# R7FA2E1A7_LED.net
KiCad netlist of a schematic drawn in EasyEDA Pro
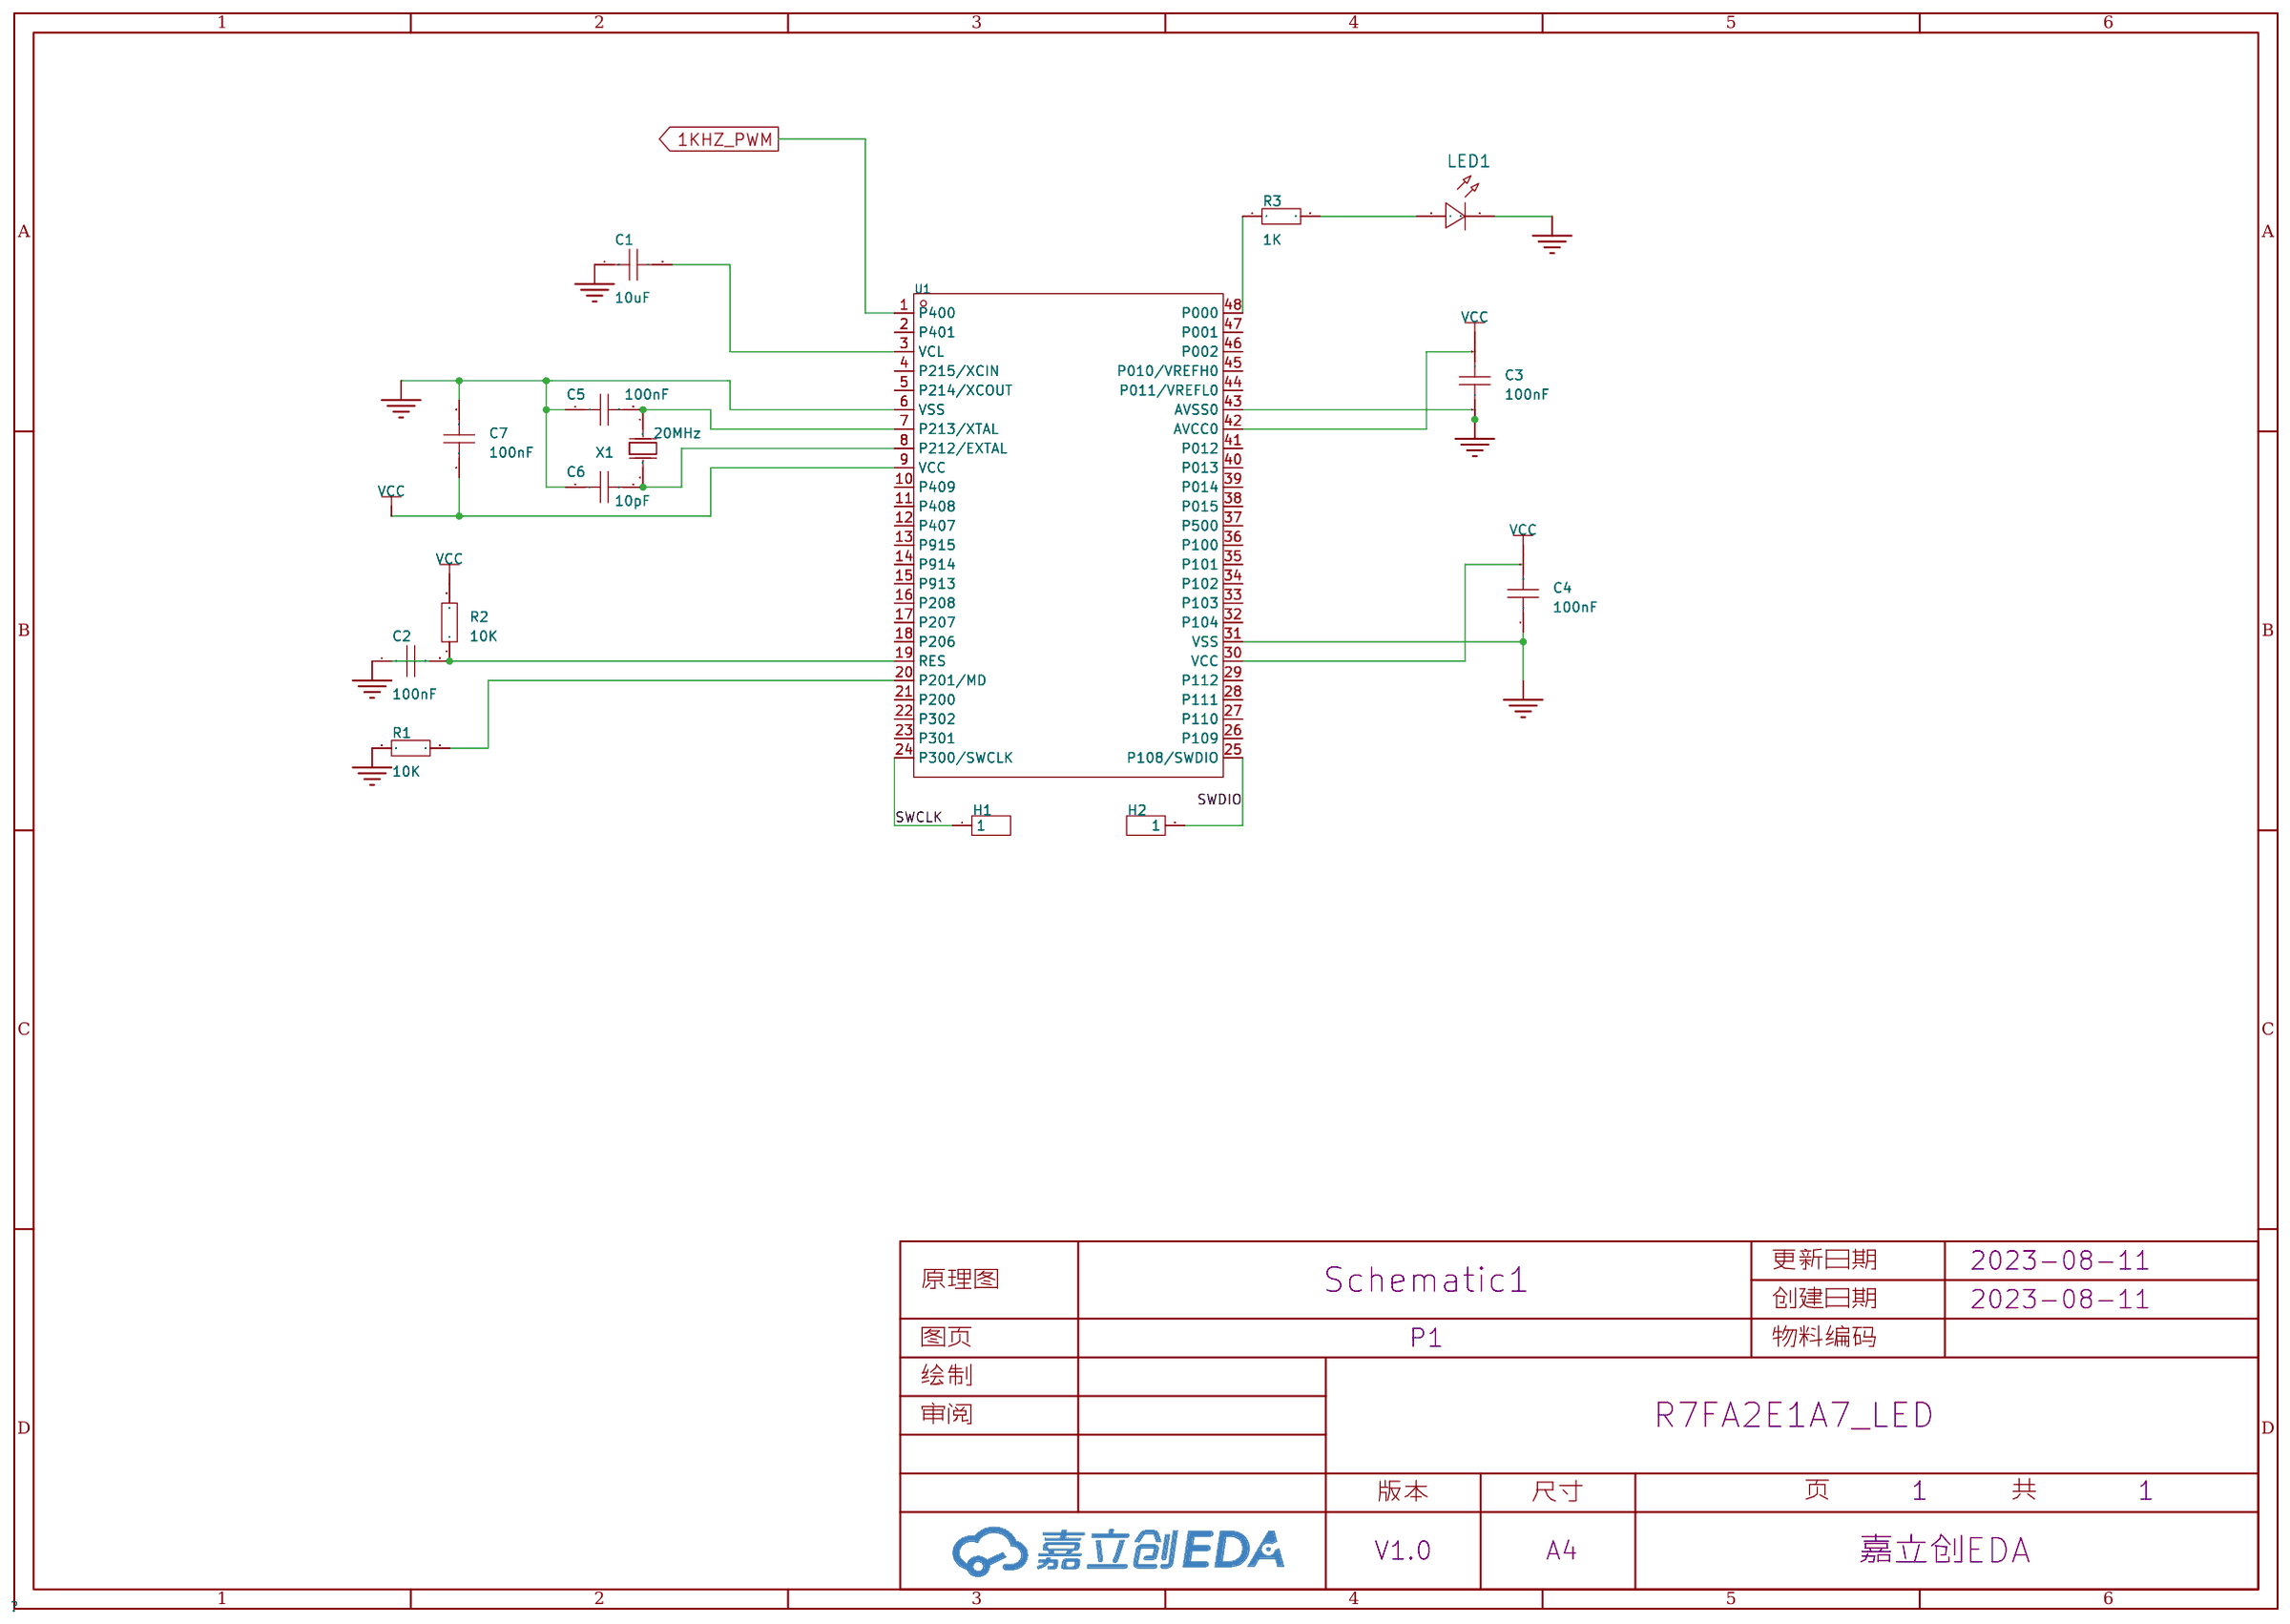
[diagram p0: schematic sheet]

(export (version "E")
  (design (tool "Eeschema 10.0.6"))
  (components
    (comp (ref "C1")
      (value "10uF")
      (footprint "easyedapro:C0603")
      (libsource (lib "easyedapro") (part "CapAcitance"))
    )
    (comp (ref "C2")
      (value "100nF")
      (footprint "easyedapro:C0603")
      (libsource (lib "easyedapro") (part "CapAcitance"))
    )
    (comp (ref "C3")
      (value "100nF")
      (footprint "easyedapro:C0603")
      (libsource (lib "easyedapro") (part "CapAcitance"))
    )
    (comp (ref "C4")
      (value "100nF")
      (footprint "easyedapro:C0603")
      (libsource (lib "easyedapro") (part "CapAcitance"))
    )
    (comp (ref "C5")
      (value "100nF")
      (footprint "easyedapro:C0603")
      (libsource (lib "easyedapro") (part "CapAcitance"))
    )
    (comp (ref "C6")
      (value "10pF")
      (footprint "easyedapro:C0603")
      (libsource (lib "easyedapro") (part "CapAcitance"))
    )
    (comp (ref "C7")
      (value "100nF")
      (footprint "easyedapro:C0603")
      (libsource (lib "easyedapro") (part "CapAcitance"))
    )
    (comp (ref "H1")
      (value "~")
      (footprint "easyedapro:HDR-TH_1P-V-M_XKB_X4611WV-01I-C28D40")
      (libsource (lib "easyedapro") (part "HDR_1x1"))
    )
    (comp (ref "H2")
      (value "~")
      (footprint "easyedapro:HDR-TH_1P-V-M_XKB_X4611WV-01I-C28D40")
      (libsource (lib "easyedapro") (part "HDR_1x1"))
    )
    (comp (ref "LED1")
      (value "~")
      (footprint "easyedapro:LED_0603")
      (libsource (lib "easyedapro") (part "LED_R"))
    )
    (comp (ref "R1") (value "10K") (footprint "easyedapro:R0603") (libsource (lib "easyedapro") (part "电阻")))
    (comp (ref "R2") (value "10K") (footprint "easyedapro:R0603") (libsource (lib "easyedapro") (part "电阻")))
    (comp (ref "R3") (value "1K") (footprint "easyedapro:R0603") (libsource (lib "easyedapro") (part "电阻")))
    (comp (ref "U1")
      (value "R7FA2E1A72DFL#AA0")
      (footprint "easyedapro:LQFP-48_L7.0-W7.0-P0.50-LS9.0-BL")
      (description "CPU内核:ARM Cortex-M23;CPU最大主频:48MHz;工作电压范围:1.6V~5.5V;程序存储容量:64KB;RAM总容量:16KB;GPIO端口数量:40;")
      (fields (field (name "Manufacturer") "RENESAS(瑞萨)/IDT"))
      (libsource (lib "easyedapro") (part "R7FA2E1A72DFL#AA0"))
    )
    (comp (ref "X1")
      (value "20MHz")
      (footprint "easyedapro:OSC-TH_L10.0-W4.5-P5.00")
      (description "频率:20MHz;频率公差:±10ppm;负载电容:15pF;")
      (fields (field (name "Manufacturer Part") "X49SD20MPB2SC") (field (name "Manufacturer") "YXC(扬兴晶振)"))
      (libsource (lib "easyedapro") (part "X49SD20MPB2SC"))
    )
  )
  (nets
    (net (code "1") (name "/SWCLK") (class "Default")
      (node (ref "H1") (pin "1") (pinfunction "1_1") (pintype "unspecified"))
      (node (ref "U1") (pin "24") (pinfunction "P300/SWCLK_24") (pintype "input"))
    )
    (net (code "2") (name "/SWDIO") (class "Default")
      (node (ref "H2") (pin "1") (pinfunction "1_1") (pintype "unspecified"))
      (node (ref "U1") (pin "25") (pinfunction "P108/SWDIO_25") (pintype "input"))
    )
    (net (code "3") (name "1KHZ_PWM") (class "Default")
      (node (ref "U1") (pin "1") (pinfunction "P400_1") (pintype "input"))
    )
    (net (code "4") (name "GND") (class "Default")
      (node (ref "C1") (pin "1") (pinfunction "1_1") (pintype "input"))
      (node (ref "C2") (pin "1") (pinfunction "1_1") (pintype "input"))
      (node (ref "C3") (pin "1") (pinfunction "1_1") (pintype "input"))
      (node (ref "C4") (pin "1") (pinfunction "1_1") (pintype "input"))
      (node (ref "C5") (pin "1") (pinfunction "1_1") (pintype "input"))
      (node (ref "C6") (pin "1") (pinfunction "1_1") (pintype "input"))
      (node (ref "C7") (pin "2") (pinfunction "2_2") (pintype "input"))
      (node (ref "LED1") (pin "1") (pinfunction "C_1") (pintype "input"))
      (node (ref "R1") (pin "1") (pinfunction "1_1") (pintype "input"))
      (node (ref "U1") (pin "31") (pinfunction "VSS_31") (pintype "input"))
      (node (ref "U1") (pin "43") (pinfunction "AVSS0_43") (pintype "input"))
      (node (ref "U1") (pin "6") (pinfunction "VSS_6") (pintype "input"))
    )
    (net (code "5") (name "Net-(LED1-A)") (class "Default")
      (node (ref "LED1") (pin "2") (pinfunction "A_2") (pintype "input"))
      (node (ref "R3") (pin "2") (pinfunction "2_2") (pintype "input"))
    )
    (net (code "6") (name "Net-(U1-P000)") (class "Default")
      (node (ref "R3") (pin "1") (pinfunction "1_1") (pintype "input"))
      (node (ref "U1") (pin "48") (pinfunction "P000_48") (pintype "input"))
    )
    (net (code "7") (name "Net-(U1-P201{slash}MD)") (class "Default")
      (node (ref "R1") (pin "2") (pinfunction "2_2") (pintype "input"))
      (node (ref "U1") (pin "20") (pinfunction "P201/MD_20") (pintype "input"))
    )
    (net (code "8") (name "Net-(U1-P212{slash}EXTAL)") (class "Default")
      (node (ref "C6") (pin "2") (pinfunction "2_2") (pintype "input"))
      (node (ref "U1") (pin "8") (pinfunction "P212/EXTAL_8") (pintype "input"))
      (node (ref "X1") (pin "2") (pinfunction "OSC2_2") (pintype "input"))
    )
    (net (code "9") (name "Net-(U1-P213{slash}XTAL)") (class "Default")
      (node (ref "C5") (pin "2") (pinfunction "2_2") (pintype "input"))
      (node (ref "U1") (pin "7") (pinfunction "P213/XTAL_7") (pintype "input"))
      (node (ref "X1") (pin "1") (pinfunction "OSC1_1") (pintype "input"))
    )
    (net (code "10") (name "Net-(U1-RES)") (class "Default")
      (node (ref "C2") (pin "2") (pinfunction "2_2") (pintype "input"))
      (node (ref "R2") (pin "1") (pinfunction "1_1") (pintype "input"))
      (node (ref "U1") (pin "19") (pinfunction "RES_19") (pintype "input"))
    )
    (net (code "11") (name "Net-(U1-VCL)") (class "Default")
      (node (ref "C1") (pin "2") (pinfunction "2_2") (pintype "input"))
      (node (ref "U1") (pin "3") (pinfunction "VCL_3") (pintype "input"))
    )
    (net (code "12") (name "VCC") (class "Default")
      (node (ref "C3") (pin "2") (pinfunction "2_2") (pintype "input"))
      (node (ref "C4") (pin "2") (pinfunction "2_2") (pintype "input"))
      (node (ref "C7") (pin "1") (pinfunction "1_1") (pintype "input"))
      (node (ref "R2") (pin "2") (pinfunction "2_2") (pintype "input"))
      (node (ref "U1") (pin "9") (pinfunction "VCC_9") (pintype "input"))
    )
    (net (code "13") (name "unconnected-(U1-AVCC0-Pad42)") (class "Default")
      (node (ref "U1") (pin "42") (pinfunction "AVCC0_42") (pintype "input"))
    )
    (net (code "14") (name "unconnected-(U1-P001-Pad47)") (class "Default")
      (node (ref "U1") (pin "47") (pinfunction "P001_47") (pintype "input"))
    )
    (net (code "15") (name "unconnected-(U1-P002-Pad46)") (class "Default")
      (node (ref "U1") (pin "46") (pinfunction "P002_46") (pintype "input"))
    )
    (net (code "16") (name "unconnected-(U1-P010{slash}VREFH0-Pad45)") (class "Default")
      (node (ref "U1") (pin "45") (pinfunction "P010/VREFH0_45") (pintype "input"))
    )
    (net (code "17") (name "unconnected-(U1-P011{slash}VREFL0-Pad44)") (class "Default")
      (node (ref "U1") (pin "44") (pinfunction "P011/VREFL0_44") (pintype "input"))
    )
    (net (code "18") (name "unconnected-(U1-P012-Pad41)") (class "Default")
      (node (ref "U1") (pin "41") (pinfunction "P012_41") (pintype "input"))
    )
    (net (code "19") (name "unconnected-(U1-P013-Pad40)") (class "Default")
      (node (ref "U1") (pin "40") (pinfunction "P013_40") (pintype "input"))
    )
    (net (code "20") (name "unconnected-(U1-P014-Pad39)") (class "Default")
      (node (ref "U1") (pin "39") (pinfunction "P014_39") (pintype "input"))
    )
    (net (code "21") (name "unconnected-(U1-P015-Pad38)") (class "Default")
      (node (ref "U1") (pin "38") (pinfunction "P015_38") (pintype "input"))
    )
    (net (code "22") (name "unconnected-(U1-P100-Pad36)") (class "Default")
      (node (ref "U1") (pin "36") (pinfunction "P100_36") (pintype "input"))
    )
    (net (code "23") (name "unconnected-(U1-P101-Pad35)") (class "Default")
      (node (ref "U1") (pin "35") (pinfunction "P101_35") (pintype "input"))
    )
    (net (code "24") (name "unconnected-(U1-P102-Pad34)") (class "Default")
      (node (ref "U1") (pin "34") (pinfunction "P102_34") (pintype "input"))
    )
    (net (code "25") (name "unconnected-(U1-P103-Pad33)") (class "Default")
      (node (ref "U1") (pin "33") (pinfunction "P103_33") (pintype "input"))
    )
    (net (code "26") (name "unconnected-(U1-P104-Pad32)") (class "Default")
      (node (ref "U1") (pin "32") (pinfunction "P104_32") (pintype "input"))
    )
    (net (code "27") (name "unconnected-(U1-P109-Pad26)") (class "Default")
      (node (ref "U1") (pin "26") (pinfunction "P109_26") (pintype "input"))
    )
    (net (code "28") (name "unconnected-(U1-P110-Pad27)") (class "Default")
      (node (ref "U1") (pin "27") (pinfunction "P110_27") (pintype "input"))
    )
    (net (code "29") (name "unconnected-(U1-P111-Pad28)") (class "Default")
      (node (ref "U1") (pin "28") (pinfunction "P111_28") (pintype "input"))
    )
    (net (code "30") (name "unconnected-(U1-P112-Pad29)") (class "Default")
      (node (ref "U1") (pin "29") (pinfunction "P112_29") (pintype "input"))
    )
    (net (code "31") (name "unconnected-(U1-P200-Pad21)") (class "Default")
      (node (ref "U1") (pin "21") (pinfunction "P200_21") (pintype "input"))
    )
    (net (code "32") (name "unconnected-(U1-P206-Pad18)") (class "Default")
      (node (ref "U1") (pin "18") (pinfunction "P206_18") (pintype "input"))
    )
    (net (code "33") (name "unconnected-(U1-P207-Pad17)") (class "Default")
      (node (ref "U1") (pin "17") (pinfunction "P207_17") (pintype "input"))
    )
    (net (code "34") (name "unconnected-(U1-P208-Pad16)") (class "Default")
      (node (ref "U1") (pin "16") (pinfunction "P208_16") (pintype "input"))
    )
    (net (code "35") (name "unconnected-(U1-P214{slash}XCOUT-Pad5)") (class "Default")
      (node (ref "U1") (pin "5") (pinfunction "P214/XCOUT_5") (pintype "input"))
    )
    (net (code "36") (name "unconnected-(U1-P215{slash}XCIN-Pad4)") (class "Default")
      (node (ref "U1") (pin "4") (pinfunction "P215/XCIN_4") (pintype "input"))
    )
    (net (code "37") (name "unconnected-(U1-P301-Pad23)") (class "Default")
      (node (ref "U1") (pin "23") (pinfunction "P301_23") (pintype "input"))
    )
    (net (code "38") (name "unconnected-(U1-P302-Pad22)") (class "Default")
      (node (ref "U1") (pin "22") (pinfunction "P302_22") (pintype "input"))
    )
    (net (code "39") (name "unconnected-(U1-P401-Pad2)") (class "Default")
      (node (ref "U1") (pin "2") (pinfunction "P401_2") (pintype "input"))
    )
    (net (code "40") (name "unconnected-(U1-P407-Pad12)") (class "Default")
      (node (ref "U1") (pin "12") (pinfunction "P407_12") (pintype "input"))
    )
    (net (code "41") (name "unconnected-(U1-P408-Pad11)") (class "Default")
      (node (ref "U1") (pin "11") (pinfunction "P408_11") (pintype "input"))
    )
    (net (code "42") (name "unconnected-(U1-P409-Pad10)") (class "Default")
      (node (ref "U1") (pin "10") (pinfunction "P409_10") (pintype "input"))
    )
    (net (code "43") (name "unconnected-(U1-P500-Pad37)") (class "Default")
      (node (ref "U1") (pin "37") (pinfunction "P500_37") (pintype "input"))
    )
    (net (code "44") (name "unconnected-(U1-P913-Pad15)") (class "Default")
      (node (ref "U1") (pin "15") (pinfunction "P913_15") (pintype "input"))
    )
    (net (code "45") (name "unconnected-(U1-P914-Pad14)") (class "Default")
      (node (ref "U1") (pin "14") (pinfunction "P914_14") (pintype "input"))
    )
    (net (code "46") (name "unconnected-(U1-P915-Pad13)") (class "Default")
      (node (ref "U1") (pin "13") (pinfunction "P915_13") (pintype "input"))
    )
    (net (code "47") (name "unconnected-(U1-VCC-Pad30)") (class "Default")
      (node (ref "U1") (pin "30") (pinfunction "VCC_30") (pintype "input"))
    )
  )
)
